# 07.net
KiCad netlist of a schematic drawn in Altium Designer
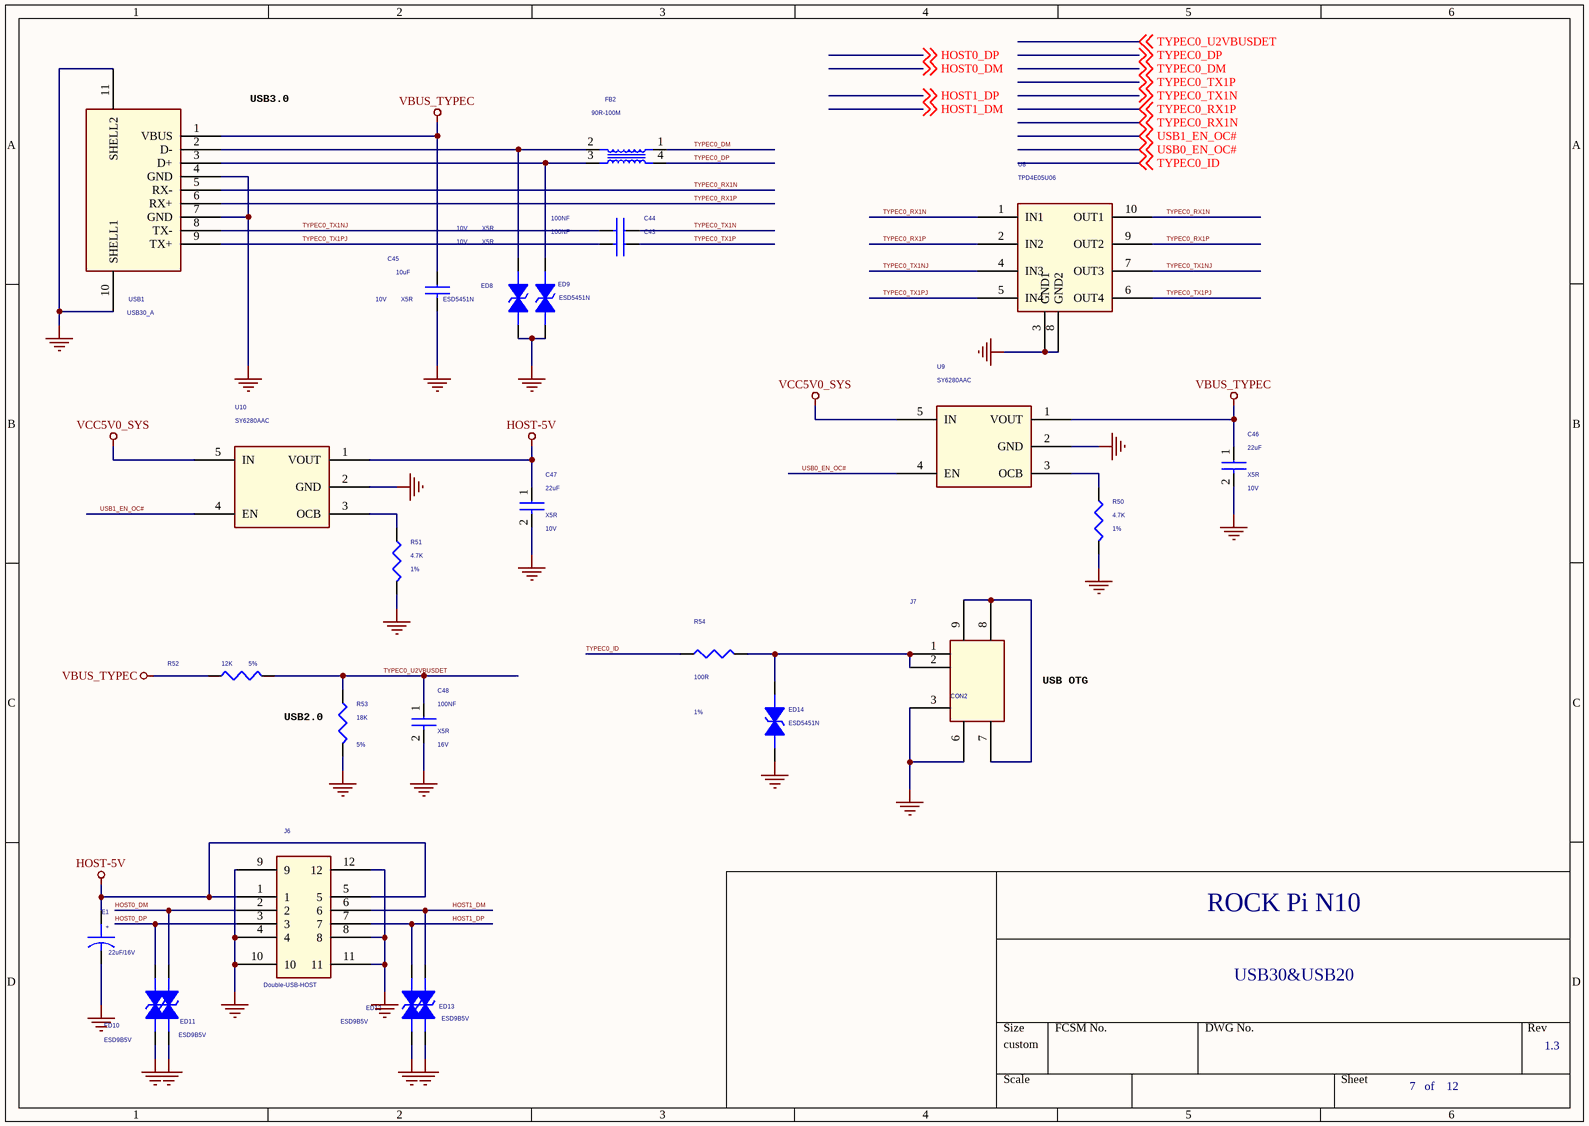
[diagram p0: 07.SchDoc]

(export (version "E")
  (design (tool "Eeschema 10.0.6"))
  (components
    (comp (ref "C43")
      (value "100NF")
      (footprint "C0402")
      (description "cap,100.00nF,+/-10%,10V,X5R,C0201")
      (fields
        (field (name "DIELECTRIC") "X5R")
        (field (name "VOLTAGE") "10V")
        (field (name "TOLERANCE") "10%")
        (field (name "MANUFACTURER") "TDK")
        (field (name "CREATED BY") "JJJ")
      )
      (libsource (lib "*") (part "CAP NP_2"))
    )
    (comp (ref "C44")
      (value "100NF")
      (footprint "C0402")
      (description "cap,100.00nF,+/-10%,10V,X5R,C0201")
      (fields
        (field (name "DIELECTRIC") "X5R")
        (field (name "VOLTAGE") "10V")
        (field (name "MANUFACTURER") "TDK")
        (field (name "TOLERANCE") "10%")
        (field (name "CREATED BY") "JJJ")
      )
      (libsource (lib "*") (part "CAP NP_2"))
    )
    (comp (ref "C45")
      (value "10uF")
      (footprint "C0603")
      (description "cap,10.00uF,+/-10%,10V,X5R,C0805")
      (fields
        (field (name "DIELECTRIC") "X5R")
        (field (name "VOLTAGE") "10V")
        (field (name "TOLERANCE") "10%")
        (field (name "MANUFACTURER") "TDK")
        (field (name "CREATED BY") "JJJ")
      )
      (libsource (lib "*") (part "CAP NP_2"))
    )
    (comp (ref "C46")
      (value "22uF")
      (footprint "C0805")
      (description "cap,10.00uF,+/-10%,10V,X5R,C0805")
      (fields
        (field (name "VOLTAGE") "10V")
        (field (name "DIELECTRIC") "X5R")
        (field (name "TOLERANCE") "10%")
        (field (name "MANUFACTURER") "TDK")
        (field (name "CREATED BY") "JJJ")
      )
      (libsource (lib "*") (part "CAP NP_1"))
    )
    (comp (ref "C47")
      (value "22uF")
      (footprint "C0805")
      (description "cap,10.00uF,+/-10%,10V,X5R,C0805")
      (fields
        (field (name "VOLTAGE") "10V")
        (field (name "DIELECTRIC") "X5R")
        (field (name "TOLERANCE") "10%")
        (field (name "MANUFACTURER") "TDK")
        (field (name "CREATED BY") "JJJ")
      )
      (libsource (lib "*") (part "CAP NP_1"))
    )
    (comp (ref "C48")
      (value "100NF")
      (footprint "C0402")
      (description "cap,100.00nF,+/-10%,16V,X5R,C0402")
      (fields
        (field (name "VOLTAGE") "16V")
        (field (name "DIELECTRIC") "X5R")
        (field (name "TOLERANCE") "10%")
        (field (name "MANUFACTURER") "TDK")
        (field (name "CREATED BY") "JJJ")
      )
      (libsource (lib "*") (part "CAP NP_1"))
    )
    (comp (ref "E1") (value "22uF/16V") (footprint "C0805") (libsource (lib "*") (part "CAPACITOR POL")))
    (comp (ref "ED8")
      (value "ESD5451N")
      (footprint "E0402N")
      (description "1-Line, Bi-directional, Transient Voltage Suppressors.17.5pF.")
      (fields (field (name "MANUFACTURER") "WillSemi(韦尔半导体)") (field (name "CREATED BY") "JJJ"))
      (libsource (lib "*") (part "DIODE BI_DIR TRIG_0"))
    )
    (comp (ref "ED9")
      (value "ESD5451N")
      (footprint "E0402N")
      (description "1-Line, Bi-directional, Transient Voltage Suppressors.17.5pF.")
      (fields (field (name "MANUFACTURER") "WillSemi(韦尔半导体)") (field (name "CREATED BY") "JJJ"))
      (libsource (lib "*") (part "DIODE BI_DIR TRIG_0"))
    )
    (comp (ref "ED10")
      (value "ESD9B5V")
      (footprint "E0402")
      (description "ESD Component,5V,0.5P,SMD,0402")
      (libsource (lib "*") (part "DIODE_TVS"))
    )
    (comp (ref "ED11")
      (value "ESD9B5V")
      (footprint "E0402")
      (description "ESD Component,5V,0.5P,SMD,0402")
      (libsource (lib "*") (part "DIODE_TVS"))
    )
    (comp (ref "ED12")
      (value "ESD9B5V")
      (footprint "E0402")
      (description "ESD Component,5V,0.5P,SMD,0402")
      (libsource (lib "*") (part "DIODE_TVS"))
    )
    (comp (ref "ED13")
      (value "ESD9B5V")
      (footprint "E0402")
      (description "ESD Component,5V,0.5P,SMD,0402")
      (libsource (lib "*") (part "DIODE_TVS"))
    )
    (comp (ref "ED14")
      (value "ESD5451N")
      (footprint "E0402N")
      (description "1-Line, Bi-directional, Transient Voltage Suppressors.17.5pF.")
      (fields (field (name "MANUFACTURER") "WillSemi(韦尔半导体)") (field (name "CREATED BY") "JJJ"))
      (libsource (lib "*") (part "DIODE BI_DIR TRIG_0"))
    )
    (comp (ref "FB2") (value "90R-100M") (footprint "COMMON-COIL4P") (libsource (lib "*") (part "R-PACK4_3")))
    (comp (ref "J6") (value "Double-USB-HOST") (footprint "USB_DUAL") (libsource (lib "*") (part "CON4_1")))
    (comp (ref "J7") (value "CON2") (footprint "LD-020") (libsource (lib "*") (part "CON2_2")))
    (comp (ref "R50")
      (value "4.7K")
      (footprint "R0402")
      (description "通用厚膜电阻,4K7,+/-1%,R0402,1/16W.")
      (fields
        (field (name "TOLERANCE") "1%")
        (field (name "MANUFACTURER") "YAGEO")
        (field (name "CREATED BY") "YTL")
      )
      (libsource (lib "*") (part "RESISTOR_3"))
    )
    (comp (ref "R51")
      (value "4.7K")
      (footprint "R0402")
      (description "通用厚膜电阻,4K7,+/-1%,R0402,1/16W.")
      (fields
        (field (name "TOLERANCE") "1%")
        (field (name "MANUFACTURER") "YAGEO")
        (field (name "CREATED BY") "YTL")
      )
      (libsource (lib "*") (part "RESISTOR_3"))
    )
    (comp (ref "R52")
      (value "12K")
      (footprint "R0402")
      (description "通用厚膜电阻,10K,+/-5%,R0402,1/16W.")
      (fields
        (field (name "TOLERANCE") "5%")
        (field (name "MANUFACTURER") "YAGEO")
        (field (name "CREATED BY") "YTL")
      )
      (libsource (lib "*") (part "RESISTOR_3"))
    )
    (comp (ref "R53")
      (value "18K")
      (footprint "R0402")
      (description "通用厚膜电阻,15K,+/-5%,R0402,1/16W.")
      (fields
        (field (name "TOLERANCE") "5%")
        (field (name "MANUFACTURER") "YAGEO")
        (field (name "CREATED BY") "YTL")
      )
      (libsource (lib "*") (part "RESISTOR_3"))
    )
    (comp (ref "R54")
      (value "100R")
      (footprint "R0402")
      (description "通用厚膜电阻,4K7,+/-1%,R0402,1/16W.")
      (fields
        (field (name "TOLERANCE") "1%")
        (field (name "MANUFACTURER") "YAGEO")
        (field (name "CREATED BY") "YTL")
      )
      (libsource (lib "*") (part "RESISTOR_3"))
    )
    (comp (ref "U8")
      (value "TPD4E05U06")
      (footprint "SON10_2R50X1R00X0R50")
      (description "unidirectional ESD protection devices with ultra low capacitance")
      (fields (field (name "MANUFACTURER") "TI（德州仪器）") (field (name "CREATED BY") "JJJ"))
      (libsource (lib "*") (part "ESD_TPD4E05U06"))
    )
    (comp (ref "U9")
      (value "SY6280AAC")
      (footprint "SOT25")
      (description "Low Loss Power Distribution Switch")
      (fields (field (name "MANUFACTURER") "Silergy（矽力杰）") (field (name "CREATED BY") "JJJ"))
      (libsource (lib "*") (part "SWITCH_SY6280"))
    )
    (comp (ref "U10")
      (value "SY6280AAC")
      (footprint "SOT25")
      (description "Low Loss Power Distribution Switch")
      (fields (field (name "MANUFACTURER") "Silergy（矽力杰）") (field (name "CREATED BY") "JJJ"))
      (libsource (lib "*") (part "SWITCH_SY6280"))
    )
    (comp (ref "USB1")
      (value "USB30_A")
      (footprint "USB30")
      (description "A型USB3.0座，卧式，插焊")
      (fields (field (name "MANUFACTURER") "旺科达") (field (name "CREATED BY") "JJJ"))
      (libsource (lib "*") (part "USB30_TYPE_A"))
    )
  )
  (nets
    (net (code "1") (name "/TYPEC0_TX1NJ") (class "Default")
      (node (ref "C44") (pin "2") (pinfunction "2_2") (pintype "passive"))
      (node (ref "U8") (pin "4") (pinfunction "IN3_4") (pintype "passive"))
      (node (ref "U8") (pin "7") (pinfunction "OUT3_7") (pintype "passive"))
      (node (ref "USB1") (pin "8") (pinfunction "TX-_8") (pintype "passive"))
    )
    (net (code "2") (name "/TYPEC0_TX1PJ") (class "Default")
      (node (ref "C43") (pin "2") (pinfunction "2_2") (pintype "passive"))
      (node (ref "U8") (pin "5") (pinfunction "IN4_5") (pintype "passive"))
      (node (ref "U8") (pin "6") (pinfunction "OUT4_6") (pintype "passive"))
      (node (ref "USB1") (pin "9") (pinfunction "TX+_9") (pintype "passive"))
    )
    (net (code "3") (name "GND") (class "Default")
      (node (ref "C45") (pin "2") (pinfunction "2_2") (pintype "passive"))
      (node (ref "C46") (pin "2") (pinfunction "2_2") (pintype "passive"))
      (node (ref "C47") (pin "2") (pinfunction "2_2") (pintype "passive"))
      (node (ref "C48") (pin "2") (pinfunction "2_2") (pintype "passive"))
      (node (ref "E1") (pin "2") (pinfunction "2_2") (pintype "passive"))
      (node (ref "ED10") (pin "2") (pinfunction "2_2") (pintype "passive"))
      (node (ref "ED11") (pin "2") (pinfunction "2_2") (pintype "passive"))
      (node (ref "ED12") (pin "2") (pinfunction "2_2") (pintype "passive"))
      (node (ref "ED13") (pin "2") (pinfunction "2_2") (pintype "passive"))
      (node (ref "ED14") (pin "2") (pinfunction "2_2") (pintype "passive"))
      (node (ref "ED8") (pin "2") (pinfunction "2_2") (pintype "passive"))
      (node (ref "ED9") (pin "2") (pinfunction "2_2") (pintype "passive"))
      (node (ref "J6") (pin "10") (pinfunction "10_10") (pintype "passive"))
      (node (ref "J6") (pin "11") (pinfunction "11_11") (pintype "passive"))
      (node (ref "J6") (pin "12") (pinfunction "12_12") (pintype "passive"))
      (node (ref "J6") (pin "4") (pinfunction "4_4") (pintype "passive"))
      (node (ref "J6") (pin "8") (pinfunction "8_8") (pintype "passive"))
      (node (ref "J6") (pin "9") (pinfunction "9_9") (pintype "passive"))
      (node (ref "J7") (pin "3") (pinfunction "3_3") (pintype "passive"))
      (node (ref "J7") (pin "6") (pinfunction "6_6") (pintype "passive"))
      (node (ref "R50") (pin "2") (pinfunction "2_2") (pintype "passive"))
      (node (ref "R51") (pin "2") (pinfunction "2_2") (pintype "passive"))
      (node (ref "R53") (pin "2") (pinfunction "2_2") (pintype "passive"))
      (node (ref "U10") (pin "2") (pinfunction "GND_2") (pintype "passive"))
      (node (ref "U8") (pin "3") (pinfunction "GND1_3") (pintype "passive"))
      (node (ref "U8") (pin "8") (pinfunction "GND2_8") (pintype "passive"))
      (node (ref "U9") (pin "2") (pinfunction "GND_2") (pintype "passive"))
      (node (ref "USB1") (pin "10") (pinfunction "SHELL1_10") (pintype "passive"))
      (node (ref "USB1") (pin "11") (pinfunction "SHELL2_11") (pintype "passive"))
      (node (ref "USB1") (pin "4") (pinfunction "GND_4") (pintype "power_in"))
      (node (ref "USB1") (pin "7") (pinfunction "GND_7") (pintype "power_in"))
    )
    (net (code "4") (name "HOST-5V") (class "Default")
      (node (ref "C47") (pin "1") (pinfunction "1_1") (pintype "passive"))
      (node (ref "E1") (pin "1") (pinfunction "1_1") (pintype "passive"))
      (node (ref "J6") (pin "1") (pinfunction "1_1") (pintype "passive"))
      (node (ref "J6") (pin "5") (pinfunction "5_5") (pintype "passive"))
      (node (ref "U10") (pin "1") (pinfunction "VOUT_1") (pintype "passive"))
    )
    (net (code "5") (name "HOST0_DM") (class "Default")
      (node (ref "ED11") (pin "1") (pinfunction "1_1") (pintype "passive"))
      (node (ref "J6") (pin "2") (pinfunction "2_2") (pintype "passive"))
    )
    (net (code "6") (name "HOST0_DP") (class "Default")
      (node (ref "ED10") (pin "1") (pinfunction "1_1") (pintype "passive"))
      (node (ref "J6") (pin "3") (pinfunction "3_3") (pintype "passive"))
    )
    (net (code "7") (name "HOST1_DM") (class "Default")
      (node (ref "ED13") (pin "1") (pinfunction "1_1") (pintype "passive"))
      (node (ref "J6") (pin "6") (pinfunction "6_6") (pintype "passive"))
    )
    (net (code "8") (name "HOST1_DP") (class "Default")
      (node (ref "ED12") (pin "1") (pinfunction "1_1") (pintype "passive"))
      (node (ref "J6") (pin "7") (pinfunction "7_7") (pintype "passive"))
    )
    (net (code "9") (name "Net-(ED14-Pad1)") (class "Default")
      (node (ref "ED14") (pin "1") (pinfunction "1_1") (pintype "passive"))
      (node (ref "J7") (pin "1") (pinfunction "1_1") (pintype "passive"))
      (node (ref "J7") (pin "2") (pinfunction "2_2") (pintype "passive"))
      (node (ref "R54") (pin "2") (pinfunction "2_2") (pintype "passive"))
    )
    (net (code "10") (name "Net-(FB2-R3)") (class "Default")
      (node (ref "ED9") (pin "1") (pinfunction "1_1") (pintype "passive"))
      (node (ref "FB2") (pin "3") (pinfunction "R3_3") (pintype "passive"))
      (node (ref "USB1") (pin "3") (pinfunction "D+_3") (pintype "passive"))
    )
    (net (code "11") (name "Net-(FB2-R4)") (class "Default")
      (node (ref "ED8") (pin "1") (pinfunction "1_1") (pintype "passive"))
      (node (ref "FB2") (pin "2") (pinfunction "R4_2") (pintype "passive"))
      (node (ref "USB1") (pin "2") (pinfunction "D-_2") (pintype "passive"))
    )
    (net (code "12") (name "Net-(J7-Pad7)") (class "Default")
      (node (ref "J7") (pin "7") (pinfunction "7_7") (pintype "passive"))
      (node (ref "J7") (pin "8") (pinfunction "8_8") (pintype "passive"))
      (node (ref "J7") (pin "9") (pinfunction "9_9") (pintype "passive"))
    )
    (net (code "13") (name "Net-(U9-OCB)") (class "Default")
      (node (ref "R50") (pin "1") (pinfunction "1_1") (pintype "passive"))
      (node (ref "U9") (pin "3") (pinfunction "OCB_3") (pintype "passive"))
    )
    (net (code "14") (name "Net-(U10-OCB)") (class "Default")
      (node (ref "R51") (pin "1") (pinfunction "1_1") (pintype "passive"))
      (node (ref "U10") (pin "3") (pinfunction "OCB_3") (pintype "passive"))
    )
    (net (code "15") (name "TYPEC0_DM") (class "Default")
      (node (ref "FB2") (pin "1") (pinfunction "R1_1") (pintype "passive"))
    )
    (net (code "16") (name "TYPEC0_DP") (class "Default")
      (node (ref "FB2") (pin "4") (pinfunction "R2_4") (pintype "passive"))
    )
    (net (code "17") (name "TYPEC0_ID") (class "Default")
      (node (ref "R54") (pin "1") (pinfunction "1_1") (pintype "passive"))
    )
    (net (code "18") (name "TYPEC0_RX1N") (class "Default")
      (node (ref "U8") (pin "1") (pinfunction "IN1_1") (pintype "passive"))
      (node (ref "U8") (pin "10") (pinfunction "OUT1_10") (pintype "passive"))
      (node (ref "USB1") (pin "5") (pinfunction "RX-_5") (pintype "passive"))
    )
    (net (code "19") (name "TYPEC0_RX1P") (class "Default")
      (node (ref "U8") (pin "2") (pinfunction "IN2_2") (pintype "passive"))
      (node (ref "U8") (pin "9") (pinfunction "OUT2_9") (pintype "passive"))
      (node (ref "USB1") (pin "6") (pinfunction "RX+_6") (pintype "passive"))
    )
    (net (code "20") (name "TYPEC0_TX1N") (class "Default")
      (node (ref "C44") (pin "1") (pinfunction "1_1") (pintype "passive"))
    )
    (net (code "21") (name "TYPEC0_TX1P") (class "Default")
      (node (ref "C43") (pin "1") (pinfunction "1_1") (pintype "passive"))
    )
    (net (code "22") (name "TYPEC0_U2VBUSDET") (class "Default")
      (node (ref "C48") (pin "1") (pinfunction "1_1") (pintype "passive"))
      (node (ref "R52") (pin "2") (pinfunction "2_2") (pintype "passive"))
      (node (ref "R53") (pin "1") (pinfunction "1_1") (pintype "passive"))
    )
    (net (code "23") (name "USB0_EN_OC#") (class "Default")
      (node (ref "U9") (pin "4") (pinfunction "EN_4") (pintype "passive"))
    )
    (net (code "24") (name "USB1_EN_OC#") (class "Default")
      (node (ref "U10") (pin "4") (pinfunction "EN_4") (pintype "passive"))
    )
    (net (code "25") (name "VBUS_TYPEC") (class "Default")
      (node (ref "C45") (pin "1") (pinfunction "1_1") (pintype "passive"))
      (node (ref "C46") (pin "1") (pinfunction "1_1") (pintype "passive"))
      (node (ref "R52") (pin "1") (pinfunction "1_1") (pintype "passive"))
      (node (ref "U9") (pin "1") (pinfunction "VOUT_1") (pintype "passive"))
      (node (ref "USB1") (pin "1") (pinfunction "VBUS_1") (pintype "power_in"))
    )
    (net (code "26") (name "VCC5V0_SYS") (class "Default")
      (node (ref "U10") (pin "5") (pinfunction "IN_5") (pintype "passive"))
      (node (ref "U9") (pin "5") (pinfunction "IN_5") (pintype "passive"))
    )
  )
)
